# leptanie_tl_hore.net
KiCad netlist of a schematic drawn in EAGLE
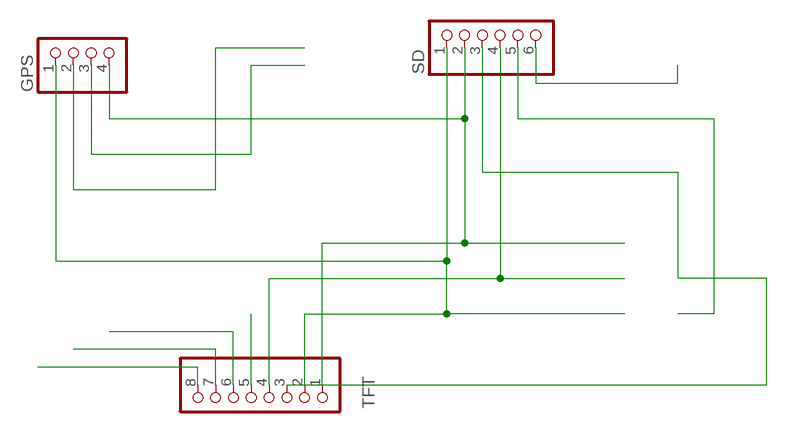
[diagram p0: schematic, sheet 1]

(export (version "E")
  (design (tool "Eeschema 10.0.6"))
  (components
    (comp (ref "GPS")
      (value "PINHD-1X4")
      (footprint "eagle-import:1X04")
      (libsource (lib "eagle-import") (part "PINHD-1X4"))
    )
    (comp (ref "SD")
      (value "PINHD-1X6")
      (footprint "eagle-import:1X06")
      (libsource (lib "eagle-import") (part "PINHD-1X6"))
    )
    (comp (ref "TFT")
      (value "PINHD-1X8")
      (footprint "eagle-import:1X08")
      (libsource (lib "eagle-import") (part "PINHD-1X8"))
    )
  )
  (nets
    (net (code "1") (name "Net-(GPS-Pad1)") (class "Default")
      (node (ref "GPS") (pin "1") (pinfunction "1_1") (pintype "passive"))
      (node (ref "SD") (pin "1") (pinfunction "1_1") (pintype "passive"))
      (node (ref "TFT") (pin "2") (pinfunction "2_2") (pintype "passive"))
    )
    (net (code "2") (name "Net-(GPS-Pad4)") (class "Default")
      (node (ref "GPS") (pin "4") (pinfunction "4_4") (pintype "passive"))
      (node (ref "SD") (pin "2") (pinfunction "2_2") (pintype "passive"))
      (node (ref "TFT") (pin "1") (pinfunction "1_1") (pintype "passive"))
    )
    (net (code "3") (name "Net-(SD-Pad3)") (class "Default")
      (node (ref "SD") (pin "3") (pinfunction "3_3") (pintype "passive"))
      (node (ref "TFT") (pin "3") (pinfunction "3_3") (pintype "passive"))
    )
    (net (code "4") (name "Net-(SD-Pad4)") (class "Default")
      (node (ref "SD") (pin "4") (pinfunction "4_4") (pintype "passive"))
      (node (ref "TFT") (pin "4") (pinfunction "4_4") (pintype "passive"))
    )
    (net (code "5") (name "unconnected-(GPS-Pad2)") (class "Default")
      (node (ref "GPS") (pin "2") (pinfunction "2_2") (pintype "passive"))
    )
    (net (code "6") (name "unconnected-(GPS-Pad3)") (class "Default")
      (node (ref "GPS") (pin "3") (pinfunction "3_3") (pintype "passive"))
    )
    (net (code "7") (name "unconnected-(SD-Pad5)") (class "Default")
      (node (ref "SD") (pin "5") (pinfunction "5_5") (pintype "passive"))
    )
    (net (code "8") (name "unconnected-(SD-Pad6)") (class "Default")
      (node (ref "SD") (pin "6") (pinfunction "6_6") (pintype "passive"))
    )
    (net (code "9") (name "unconnected-(TFT-Pad5)") (class "Default")
      (node (ref "TFT") (pin "5") (pinfunction "5_5") (pintype "passive"))
    )
    (net (code "10") (name "unconnected-(TFT-Pad6)") (class "Default")
      (node (ref "TFT") (pin "6") (pinfunction "6_6") (pintype "passive"))
    )
    (net (code "11") (name "unconnected-(TFT-Pad7)") (class "Default")
      (node (ref "TFT") (pin "7") (pinfunction "7_7") (pintype "passive"))
    )
    (net (code "12") (name "unconnected-(TFT-Pad8)") (class "Default")
      (node (ref "TFT") (pin "8") (pinfunction "8_8") (pintype "passive"))
    )
  )
)
